# Mainboard_User_Interface.net
KiCad netlist of a schematic drawn in Altium Designer
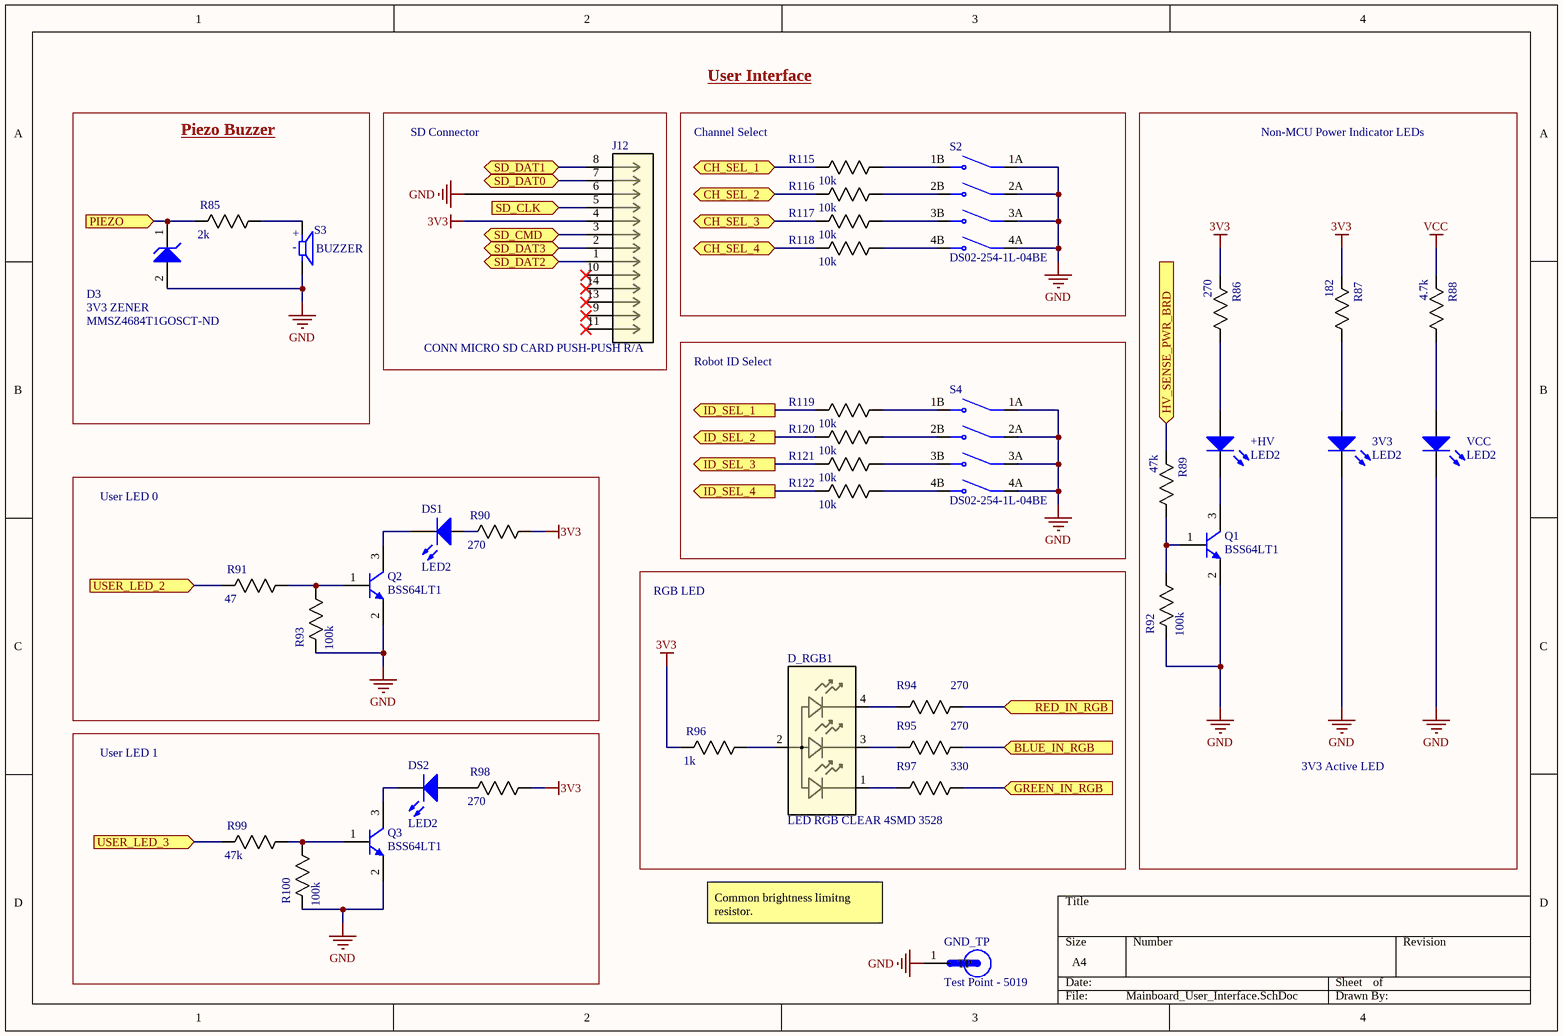
[diagram p0: Mainboard_User_Interface.SchDoc]

(export (version "E")
  (design (tool "Eeschema 10.0.6"))
  (components
    (comp (ref "+HV")
      (value "LED2")
      (footprint "3.2X1.6X1.1")
      (description "Typical RED, GREEN, YELLOW, AMBER GaAs LED")
      (libsource (lib "AltiumLibraries") (part "LED GREEN SMD"))
    )
    (comp (ref "3V3")
      (value "LED2")
      (footprint "3.2X1.6X1.1")
      (description "Typical RED, GREEN, YELLOW, AMBER GaAs LED")
      (libsource (lib "AltiumLibraries") (part "LED GREEN SMD"))
    )
    (comp (ref "D3")
      (value "3V3 ZENER")
      (footprint "ONSC-SOD-123-2-425-04_V")
      (description "Zener 3V3 Voltage Regulator, 500 mW, 2-Pin SOD-123, Pb-Free, Tape and Reel")
      (fields
        (field (name "PARTNUMBER") "MMSZ4684T1G")
        (field (name "MANUFACTURER") "On Semiconductor")
        (field (name "SUPPLIER PART NUMBER 1") "MMSZ4684T1GOSCT-ND")
      )
      (libsource (lib "AltiumLibraries") (part "DIODE ZENER 3.3 500mW"))
    )
    (comp (ref "DS1")
      (value "LED2")
      (footprint "3.2X1.6X1.1")
      (description "Typical RED, GREEN, YELLOW, AMBER GaAs LED")
      (libsource (lib "AltiumLibraries") (part "LED GREEN SMD"))
    )
    (comp (ref "DS2")
      (value "LED2")
      (footprint "3.2X1.6X1.1")
      (description "Typical RED, GREEN, YELLOW, AMBER GaAs LED")
      (libsource (lib "AltiumLibraries") (part "LED RED SMD"))
    )
    (comp (ref "D_RGB1")
      (value "LED RGB CLEAR 4SMD 3528")
      (footprint "LED 4pin 3.5 x 2.8")
      (description "LED RGB No Lead \r\nAAA3528")
      (libsource (lib "AltiumLibraries") (part "LED RGB CLEAR 4SMD 3528"))
    )
    (comp (ref "GND_TP")
      (value "Test Point - 5019")
      (footprint "TP380X203")
      (description "PC Test Point, Miniature Phosphor Bronze, Silver Plating Surface Mount Mounting Type")
      (fields (field (name "MP") "5019") (field (name "MF") "Keystone Electronics"))
      (libsource (lib "AltiumLibraries") (part "Test Point - 5019"))
    )
    (comp (ref "J12")
      (value "CONN MICRO SD CARD PUSH-PUSH R/A")
      (footprint "SD Connector 5027740891")
      (description "10 (8 + 2) Position Card Connector Secure Digital - microSD™ Surface Mount, Right Angle Gold")
      (fields (field (name "MF") "Molex") (field (name "MP") "5027740891"))
      (libsource (lib "AltiumLibraries") (part "CONN MICRO SD CARD PUSH-PUSH R/A"))
    )
    (comp (ref "Q1")
      (value "BSS64LT1")
      (footprint "ONSC-SOT-23-3-318-08_V")
      (description "Driver Transistor, NPN Silicon, 3-Pin SOT-23, Tape and Reel")
      (fields (field (name "MANUFACTURER") "On Semiconductor"))
      (libsource (lib "Altium Content Vault") (part "ONSC-NPN-B1E2C3-3"))
    )
    (comp (ref "Q2")
      (value "BSS64LT1")
      (footprint "ONSC-SOT-23-3-318-08_V")
      (description "Driver Transistor, NPN Silicon, 3-Pin SOT-23, Tape and Reel")
      (fields (field (name "MANUFACTURER") "On Semiconductor"))
      (libsource (lib "Altium Content Vault") (part "ONSC-NPN-B1E2C3-3"))
    )
    (comp (ref "Q3")
      (value "BSS64LT1")
      (footprint "ONSC-SOT-23-3-318-08_V")
      (description "Driver Transistor, NPN Silicon, 3-Pin SOT-23, Tape and Reel")
      (fields (field (name "MANUFACTURER") "On Semiconductor"))
      (libsource (lib "Altium Content Vault") (part "ONSC-NPN-B1E2C3-3"))
    )
    (comp (ref "R85")
      (value "2k")
      (footprint "0603")
      (description "RES SMD 2K OHM 5% 1/8W 0805")
      (fields (field (name "TOLERANCE") "5%"))
      (libsource (lib "AltiumLibraries") (part "RES 2k 1/8W"))
    )
    (comp (ref "R86")
      (value "270")
      (footprint "0603")
      (description "RES SMD 270 OHM 5% 1/8W 0805")
      (fields (field (name "TOLERANCE") "5%"))
      (libsource (lib "AltiumLibraries") (part "RES 270.0 1/8W"))
    )
    (comp (ref "R87")
      (value "182")
      (footprint "0603")
      (description "RES SMD 182 OHM 1% 1/8W 0805")
      (fields (field (name "TOLERANCE") "1%"))
      (libsource (lib "AltiumLibraries") (part "RES 182.0 1/8W"))
    )
    (comp (ref "R88")
      (value "4.7k")
      (footprint "0603")
      (description "RES SMD 4.7k OHM 5% 1/8W 0805")
      (fields (field (name "TOLERANCE") "5%"))
      (libsource (lib "AltiumLibraries") (part "RES 4.7k 1/8W - 5%"))
    )
    (comp (ref "R89")
      (value "47k")
      (footprint "0603")
      (description "RES SMD 47K OHM 1% 1/8W 0805")
      (fields (field (name "TOLERANCE") "1%"))
      (libsource (lib "AltiumLibraries") (part "RES 47k 1/8W - 1%"))
    )
    (comp (ref "R90")
      (value "270")
      (footprint "0603")
      (description "RES SMD 270 OHM 5% 1/8W 0805")
      (fields (field (name "TOLERANCE") "5%"))
      (libsource (lib "") (part "RES 270.0 1/8W_1"))
    )
    (comp (ref "R91")
      (value "47")
      (footprint "0603")
      (description "RES SMD 47 OHM 1% 1/8W 0805")
      (fields (field (name "TOLERANCE") "1%"))
      (libsource (lib "AltiumLibraries") (part "RES 47.0 1/8W - 1%"))
    )
    (comp (ref "R92")
      (value "100k")
      (footprint "0603")
      (description "RES SMD 100K OHM 1% 1/8W 0805")
      (fields (field (name "TOLERANCE") "1%"))
      (libsource (lib "AltiumLibraries") (part "RES 100k 1/8W - 1%"))
    )
    (comp (ref "R93")
      (value "100k")
      (footprint "0603")
      (description "RES SMD 100K OHM 1% 1/8W 0805")
      (fields (field (name "TOLERANCE") "1%"))
      (libsource (lib "") (part "RES 100k 1/8W - 1%_1"))
    )
    (comp (ref "R94")
      (value "270")
      (footprint "0603")
      (description "RES SMD 270 OHM 5% 1/8W 0805")
      (fields (field (name "TOLERANCE") "5%"))
      (libsource (lib "AltiumLibraries") (part "RES 270.0 1/8W"))
    )
    (comp (ref "R95")
      (value "270")
      (footprint "0603")
      (description "RES SMD 270 OHM 5% 1/8W 0805")
      (fields (field (name "TOLERANCE") "5%"))
      (libsource (lib "AltiumLibraries") (part "RES 270.0 1/8W"))
    )
    (comp (ref "R96")
      (value "1k")
      (footprint "0603")
      (description "RES SMD 1K OHM 5% 1/8W 0805")
      (fields (field (name "TOLERANCE") "5%"))
      (libsource (lib "AltiumLibraries") (part "RES 1k 1/8W"))
    )
    (comp (ref "R97")
      (value "330")
      (footprint "0603")
      (description "RES SMD 330 OHM 1% 1/8W 0805")
      (fields (field (name "TOLERANCE") "1%"))
      (libsource (lib "AltiumLibraries") (part "RES 330.0 1/8W - 1%"))
    )
    (comp (ref "R98")
      (value "270")
      (footprint "0603")
      (description "RES SMD 270 OHM 5% 1/8W 0805")
      (fields (field (name "TOLERANCE") "5%"))
      (libsource (lib "") (part "RES 270.0 1/8W_1"))
    )
    (comp (ref "R99")
      (value "47k")
      (footprint "0603")
      (description "RES SMD 47K OHM 1% 1/8W 0805")
      (fields (field (name "TOLERANCE") "1%"))
      (libsource (lib "AltiumLibraries") (part "RES 47k 1/8W - 1%"))
    )
    (comp (ref "R100")
      (value "100k")
      (footprint "0603")
      (description "RES SMD 100K OHM 1% 1/8W 0805")
      (fields (field (name "TOLERANCE") "1%"))
      (libsource (lib "") (part "RES 100k 1/8W - 1%_1"))
    )
    (comp (ref "R115")
      (value "10k")
      (footprint "0603")
      (description "RES SMD 10K OHM 1% 1/8W 0805")
      (fields (field (name "TOLERANCE") "1%"))
      (libsource (lib "AltiumLibraries") (part "RES 10k 1/8W - 1%"))
    )
    (comp (ref "R116")
      (value "10k")
      (footprint "0603")
      (description "RES SMD 10K OHM 1% 1/8W 0805")
      (fields (field (name "TOLERANCE") "1%"))
      (libsource (lib "AltiumLibraries") (part "RES 10k 1/8W - 1%"))
    )
    (comp (ref "R117")
      (value "10k")
      (footprint "0603")
      (description "RES SMD 10K OHM 1% 1/8W 0805")
      (fields (field (name "TOLERANCE") "1%"))
      (libsource (lib "AltiumLibraries") (part "RES 10k 1/8W - 1%"))
    )
    (comp (ref "R118")
      (value "10k")
      (footprint "0603")
      (description "RES SMD 10K OHM 1% 1/8W 0805")
      (fields (field (name "TOLERANCE") "1%"))
      (libsource (lib "AltiumLibraries") (part "RES 10k 1/8W - 1%"))
    )
    (comp (ref "R119")
      (value "10k")
      (footprint "0603")
      (description "RES SMD 10K OHM 1% 1/8W 0805")
      (fields (field (name "TOLERANCE") "1%"))
      (libsource (lib "AltiumLibraries") (part "RES 10k 1/8W - 1%"))
    )
    (comp (ref "R120")
      (value "10k")
      (footprint "0603")
      (description "RES SMD 10K OHM 1% 1/8W 0805")
      (fields (field (name "TOLERANCE") "1%"))
      (libsource (lib "AltiumLibraries") (part "RES 10k 1/8W - 1%"))
    )
    (comp (ref "R121")
      (value "10k")
      (footprint "0603")
      (description "RES SMD 10K OHM 1% 1/8W 0805")
      (fields (field (name "TOLERANCE") "1%"))
      (libsource (lib "AltiumLibraries") (part "RES 10k 1/8W - 1%"))
    )
    (comp (ref "R122")
      (value "10k")
      (footprint "0603")
      (description "RES SMD 10K OHM 1% 1/8W 0805")
      (fields (field (name "TOLERANCE") "1%"))
      (libsource (lib "AltiumLibraries") (part "RES 10k 1/8W - 1%"))
    )
    (comp (ref "S2")
      (value "DS02-254-1L-04BE")
      (footprint "SW_DS02-254-1L-04BE")
      (description "Dip Switch Piano Key 4-position")
      (libsource (lib "AltiumLibraries") (part "DS02-254-1L-04BE"))
    )
    (comp (ref "S3")
      (value "BUZZER")
      (footprint "BUZZER PKM13EPYH4000-A0")
      (description "Buzzers Transducer, Externally Driven Piezo 1.5V 4kHz 70dB @ 1.5V, 10cm Through Hole PC Pins")
      (fields (field (name "MF") "Murata") (field (name "MP") "PKM13EPYH4000-A0"))
      (libsource (lib "AltiumLibraries") (part "BUZZER PKM13EPYH4000-A0"))
    )
    (comp (ref "S4")
      (value "DS02-254-1L-04BE")
      (footprint "SW_DS02-254-1L-04BE")
      (description "Dip Switch Piano Key 4-position")
      (libsource (lib "AltiumLibraries") (part "DS02-254-1L-04BE"))
    )
    (comp (ref "VCC")
      (value "LED2")
      (footprint "3.2X1.6X1.1")
      (description "Typical RED, GREEN, YELLOW, AMBER GaAs LED")
      (libsource (lib "AltiumLibraries") (part "LED GREEN SMD"))
    )
  )
  (nets
    (net (code "1") (name "/BLUE_IN_RGB") (class "Default")
      (node (ref "R95") (pin "1") (pinfunction "R1_1") (pintype "passive"))
    )
    (net (code "2") (name "/CH_SEL_1") (class "Default")
      (node (ref "R115") (pin "2") (pinfunction "R2_2") (pintype "passive"))
    )
    (net (code "3") (name "/CH_SEL_2") (class "Default")
      (node (ref "R116") (pin "2") (pinfunction "R2_2") (pintype "passive"))
    )
    (net (code "4") (name "/CH_SEL_3") (class "Default")
      (node (ref "R117") (pin "2") (pinfunction "R2_2") (pintype "passive"))
    )
    (net (code "5") (name "/CH_SEL_4") (class "Default")
      (node (ref "R118") (pin "2") (pinfunction "R2_2") (pintype "passive"))
    )
    (net (code "6") (name "/GREEN_IN_RGB") (class "Default")
      (node (ref "R97") (pin "1") (pinfunction "R1_1") (pintype "passive"))
    )
    (net (code "7") (name "/HV_SENSE_PWR_BRD") (class "Default")
      (node (ref "R89") (pin "2") (pinfunction "R2_2") (pintype "passive"))
    )
    (net (code "8") (name "/ID_SEL_1") (class "Default")
      (node (ref "R119") (pin "2") (pinfunction "R2_2") (pintype "passive"))
    )
    (net (code "9") (name "/ID_SEL_2") (class "Default")
      (node (ref "R120") (pin "2") (pinfunction "R2_2") (pintype "passive"))
    )
    (net (code "10") (name "/ID_SEL_3") (class "Default")
      (node (ref "R121") (pin "2") (pinfunction "R2_2") (pintype "passive"))
    )
    (net (code "11") (name "/ID_SEL_4") (class "Default")
      (node (ref "R122") (pin "2") (pinfunction "R2_2") (pintype "passive"))
    )
    (net (code "12") (name "/PIEZO") (class "Default")
      (node (ref "D3") (pin "1") (pinfunction "K_1") (pintype "passive"))
      (node (ref "R85") (pin "2") (pinfunction "R2_2") (pintype "passive"))
    )
    (net (code "13") (name "/RED_IN_RGB") (class "Default")
      (node (ref "R94") (pin "1") (pinfunction "R1_1") (pintype "passive"))
    )
    (net (code "14") (name "/SD_CLK") (class "Default")
      (node (ref "J12") (pin "5") (pinfunction "5_5") (pintype "passive"))
    )
    (net (code "15") (name "/SD_CMD") (class "Default")
      (node (ref "J12") (pin "3") (pinfunction "3_3") (pintype "passive"))
    )
    (net (code "16") (name "/SD_DAT0") (class "Default")
      (node (ref "J12") (pin "7") (pinfunction "7_7") (pintype "passive"))
    )
    (net (code "17") (name "/SD_DAT1") (class "Default")
      (node (ref "J12") (pin "8") (pinfunction "8_8") (pintype "passive"))
    )
    (net (code "18") (name "/SD_DAT2") (class "Default")
      (node (ref "J12") (pin "1") (pinfunction "1_1") (pintype "passive"))
    )
    (net (code "19") (name "/SD_DAT3") (class "Default")
      (node (ref "J12") (pin "2") (pinfunction "2_2") (pintype "passive"))
    )
    (net (code "20") (name "/USER_LED_2") (class "Default")
      (node (ref "R91") (pin "2") (pinfunction "R2_2") (pintype "passive"))
    )
    (net (code "21") (name "/USER_LED_3") (class "Default")
      (node (ref "R99") (pin "2") (pinfunction "R2_2") (pintype "passive"))
    )
    (net (code "22") (name "3V3") (class "Default")
      (node (ref "J12") (pin "4") (pinfunction "4_4") (pintype "passive"))
      (node (ref "R86") (pin "2") (pinfunction "R2_2") (pintype "passive"))
      (node (ref "R87") (pin "2") (pinfunction "R2_2") (pintype "passive"))
      (node (ref "R90") (pin "1") (pinfunction "R1_1") (pintype "passive"))
      (node (ref "R96") (pin "2") (pinfunction "R2_2") (pintype "passive"))
      (node (ref "R98") (pin "1") (pinfunction "R1_1") (pintype "passive"))
    )
    (net (code "23") (name "GND") (class "Default")
      (node (ref "3V3") (pin "2") (pinfunction "K_2") (pintype "passive"))
      (node (ref "D3") (pin "2") (pinfunction "A_2") (pintype "passive"))
      (node (ref "GND_TP") (pin "1") (pinfunction "TP_1") (pintype "passive"))
      (node (ref "J12") (pin "6") (pinfunction "6_6") (pintype "passive"))
      (node (ref "Q1") (pin "2") (pinfunction "E_2") (pintype "passive"))
      (node (ref "Q2") (pin "2") (pinfunction "E_2") (pintype "passive"))
      (node (ref "Q3") (pin "2") (pinfunction "E_2") (pintype "passive"))
      (node (ref "R100") (pin "2") (pinfunction "R2_2") (pintype "passive"))
      (node (ref "R92") (pin "2") (pinfunction "R2_2") (pintype "passive"))
      (node (ref "R93") (pin "2") (pinfunction "R2_2") (pintype "passive"))
      (node (ref "S2") (pin "1A") (pinfunction "COM1_1A") (pintype "passive"))
      (node (ref "S2") (pin "2A") (pinfunction "COM2_2A") (pintype "passive"))
      (node (ref "S2") (pin "3A") (pinfunction "COM3_3A") (pintype "passive"))
      (node (ref "S2") (pin "4A") (pinfunction "COM4_4A") (pintype "passive"))
      (node (ref "S3") (pin "N") (pinfunction "N_N") (pintype "passive"))
      (node (ref "S4") (pin "1A") (pinfunction "COM1_1A") (pintype "passive"))
      (node (ref "S4") (pin "2A") (pinfunction "COM2_2A") (pintype "passive"))
      (node (ref "S4") (pin "3A") (pinfunction "COM3_3A") (pintype "passive"))
      (node (ref "S4") (pin "4A") (pinfunction "COM4_4A") (pintype "passive"))
      (node (ref "VCC") (pin "2") (pinfunction "K_2") (pintype "passive"))
    )
    (net (code "24") (name "Net-(+HV-A)") (class "Default")
      (node (ref "+HV") (pin "1") (pinfunction "A_1") (pintype "passive"))
      (node (ref "R86") (pin "1") (pinfunction "R1_1") (pintype "passive"))
    )
    (net (code "25") (name "Net-(+HV-K)") (class "Default")
      (node (ref "+HV") (pin "2") (pinfunction "K_2") (pintype "passive"))
      (node (ref "Q1") (pin "3") (pinfunction "C_3") (pintype "passive"))
    )
    (net (code "26") (name "Net-(3V3-A)") (class "Default")
      (node (ref "3V3") (pin "1") (pinfunction "A_1") (pintype "passive"))
      (node (ref "R87") (pin "1") (pinfunction "R1_1") (pintype "passive"))
    )
    (net (code "27") (name "Net-(DS1-A)") (class "Default")
      (node (ref "DS1") (pin "1") (pinfunction "A_1") (pintype "passive"))
      (node (ref "R90") (pin "2") (pinfunction "R2_2") (pintype "passive"))
    )
    (net (code "28") (name "Net-(DS1-K)") (class "Default")
      (node (ref "DS1") (pin "2") (pinfunction "K_2") (pintype "passive"))
      (node (ref "Q2") (pin "3") (pinfunction "C_3") (pintype "passive"))
    )
    (net (code "29") (name "Net-(DS2-A)") (class "Default")
      (node (ref "DS2") (pin "1") (pinfunction "A_1") (pintype "passive"))
      (node (ref "R98") (pin "2") (pinfunction "R2_2") (pintype "passive"))
    )
    (net (code "30") (name "Net-(DS2-K)") (class "Default")
      (node (ref "DS2") (pin "2") (pinfunction "K_2") (pintype "passive"))
      (node (ref "Q3") (pin "3") (pinfunction "C_3") (pintype "passive"))
    )
    (net (code "31") (name "Net-(Q1-B)") (class "Default")
      (node (ref "Q1") (pin "1") (pinfunction "B_1") (pintype "passive"))
      (node (ref "R89") (pin "1") (pinfunction "R1_1") (pintype "passive"))
      (node (ref "R92") (pin "1") (pinfunction "R1_1") (pintype "passive"))
    )
    (net (code "32") (name "Net-(Q2-B)") (class "Default")
      (node (ref "Q2") (pin "1") (pinfunction "B_1") (pintype "passive"))
      (node (ref "R91") (pin "1") (pinfunction "R1_1") (pintype "passive"))
      (node (ref "R93") (pin "1") (pinfunction "R1_1") (pintype "passive"))
    )
    (net (code "33") (name "Net-(Q3-B)") (class "Default")
      (node (ref "Q3") (pin "1") (pinfunction "B_1") (pintype "passive"))
      (node (ref "R100") (pin "1") (pinfunction "R1_1") (pintype "passive"))
      (node (ref "R99") (pin "1") (pinfunction "R1_1") (pintype "passive"))
    )
    (net (code "34") (name "Net-(R85-R1)") (class "Default")
      (node (ref "R85") (pin "1") (pinfunction "R1_1") (pintype "passive"))
      (node (ref "S3") (pin "P") (pinfunction "P_P") (pintype "passive"))
    )
    (net (code "35") (name "Net-(R88-R1)") (class "Default")
      (node (ref "R88") (pin "1") (pinfunction "R1_1") (pintype "passive"))
      (node (ref "VCC") (pin "1") (pinfunction "A_1") (pintype "passive"))
    )
    (net (code "36") (name "Net-(R94-R2)") (class "Default")
      (node (ref "D_RGB1") (pin "4") (pinfunction "4_4") (pintype "passive"))
      (node (ref "R94") (pin "2") (pinfunction "R2_2") (pintype "passive"))
    )
    (net (code "37") (name "Net-(R95-R2)") (class "Default")
      (node (ref "D_RGB1") (pin "3") (pinfunction "3_3") (pintype "passive"))
      (node (ref "R95") (pin "2") (pinfunction "R2_2") (pintype "passive"))
    )
    (net (code "38") (name "Net-(R96-R1)") (class "Default")
      (node (ref "D_RGB1") (pin "2") (pinfunction "2_2") (pintype "passive"))
      (node (ref "R96") (pin "1") (pinfunction "R1_1") (pintype "passive"))
    )
    (net (code "39") (name "Net-(R97-R2)") (class "Default")
      (node (ref "D_RGB1") (pin "1") (pinfunction "1_1") (pintype "passive"))
      (node (ref "R97") (pin "2") (pinfunction "R2_2") (pintype "passive"))
    )
    (net (code "40") (name "Net-(R115-R1)") (class "Default")
      (node (ref "R115") (pin "1") (pinfunction "R1_1") (pintype "passive"))
      (node (ref "S2") (pin "1B") (pinfunction "NO1_1B") (pintype "passive"))
    )
    (net (code "41") (name "Net-(R116-R1)") (class "Default")
      (node (ref "R116") (pin "1") (pinfunction "R1_1") (pintype "passive"))
      (node (ref "S2") (pin "2B") (pinfunction "NO2_2B") (pintype "passive"))
    )
    (net (code "42") (name "Net-(R117-R1)") (class "Default")
      (node (ref "R117") (pin "1") (pinfunction "R1_1") (pintype "passive"))
      (node (ref "S2") (pin "3B") (pinfunction "NO3_3B") (pintype "passive"))
    )
    (net (code "43") (name "Net-(R118-R1)") (class "Default")
      (node (ref "R118") (pin "1") (pinfunction "R1_1") (pintype "passive"))
      (node (ref "S2") (pin "4B") (pinfunction "NO4_4B") (pintype "passive"))
    )
    (net (code "44") (name "Net-(R119-R1)") (class "Default")
      (node (ref "R119") (pin "1") (pinfunction "R1_1") (pintype "passive"))
      (node (ref "S4") (pin "1B") (pinfunction "NO1_1B") (pintype "passive"))
    )
    (net (code "45") (name "Net-(R120-R1)") (class "Default")
      (node (ref "R120") (pin "1") (pinfunction "R1_1") (pintype "passive"))
      (node (ref "S4") (pin "2B") (pinfunction "NO2_2B") (pintype "passive"))
    )
    (net (code "46") (name "Net-(R121-R1)") (class "Default")
      (node (ref "R121") (pin "1") (pinfunction "R1_1") (pintype "passive"))
      (node (ref "S4") (pin "3B") (pinfunction "NO3_3B") (pintype "passive"))
    )
    (net (code "47") (name "Net-(R122-R1)") (class "Default")
      (node (ref "R122") (pin "1") (pinfunction "R1_1") (pintype "passive"))
      (node (ref "S4") (pin "4B") (pinfunction "NO4_4B") (pintype "passive"))
    )
    (net (code "48") (name "VCC") (class "Default")
      (node (ref "R88") (pin "2") (pinfunction "R2_2") (pintype "passive"))
    )
    (net (code "49") (name "unconnected-(J12-Pad9)") (class "Default")
      (node (ref "J12") (pin "9") (pinfunction "9_9") (pintype "passive+no_connect"))
    )
    (net (code "50") (name "unconnected-(J12-Pad10)") (class "Default")
      (node (ref "J12") (pin "10") (pinfunction "10_10") (pintype "passive+no_connect"))
    )
    (net (code "51") (name "unconnected-(J12-Pad11)") (class "Default")
      (node (ref "J12") (pin "11") (pinfunction "11_11") (pintype "passive+no_connect"))
    )
    (net (code "52") (name "unconnected-(J12-Pad13)") (class "Default")
      (node (ref "J12") (pin "13") (pinfunction "13_13") (pintype "passive+no_connect"))
    )
    (net (code "53") (name "unconnected-(J12-Pad14)") (class "Default")
      (node (ref "J12") (pin "14") (pinfunction "14_14") (pintype "passive+no_connect"))
    )
  )
)
